# EPC_FRONTAL.net
KiCad netlist of a schematic drawn in EAGLE
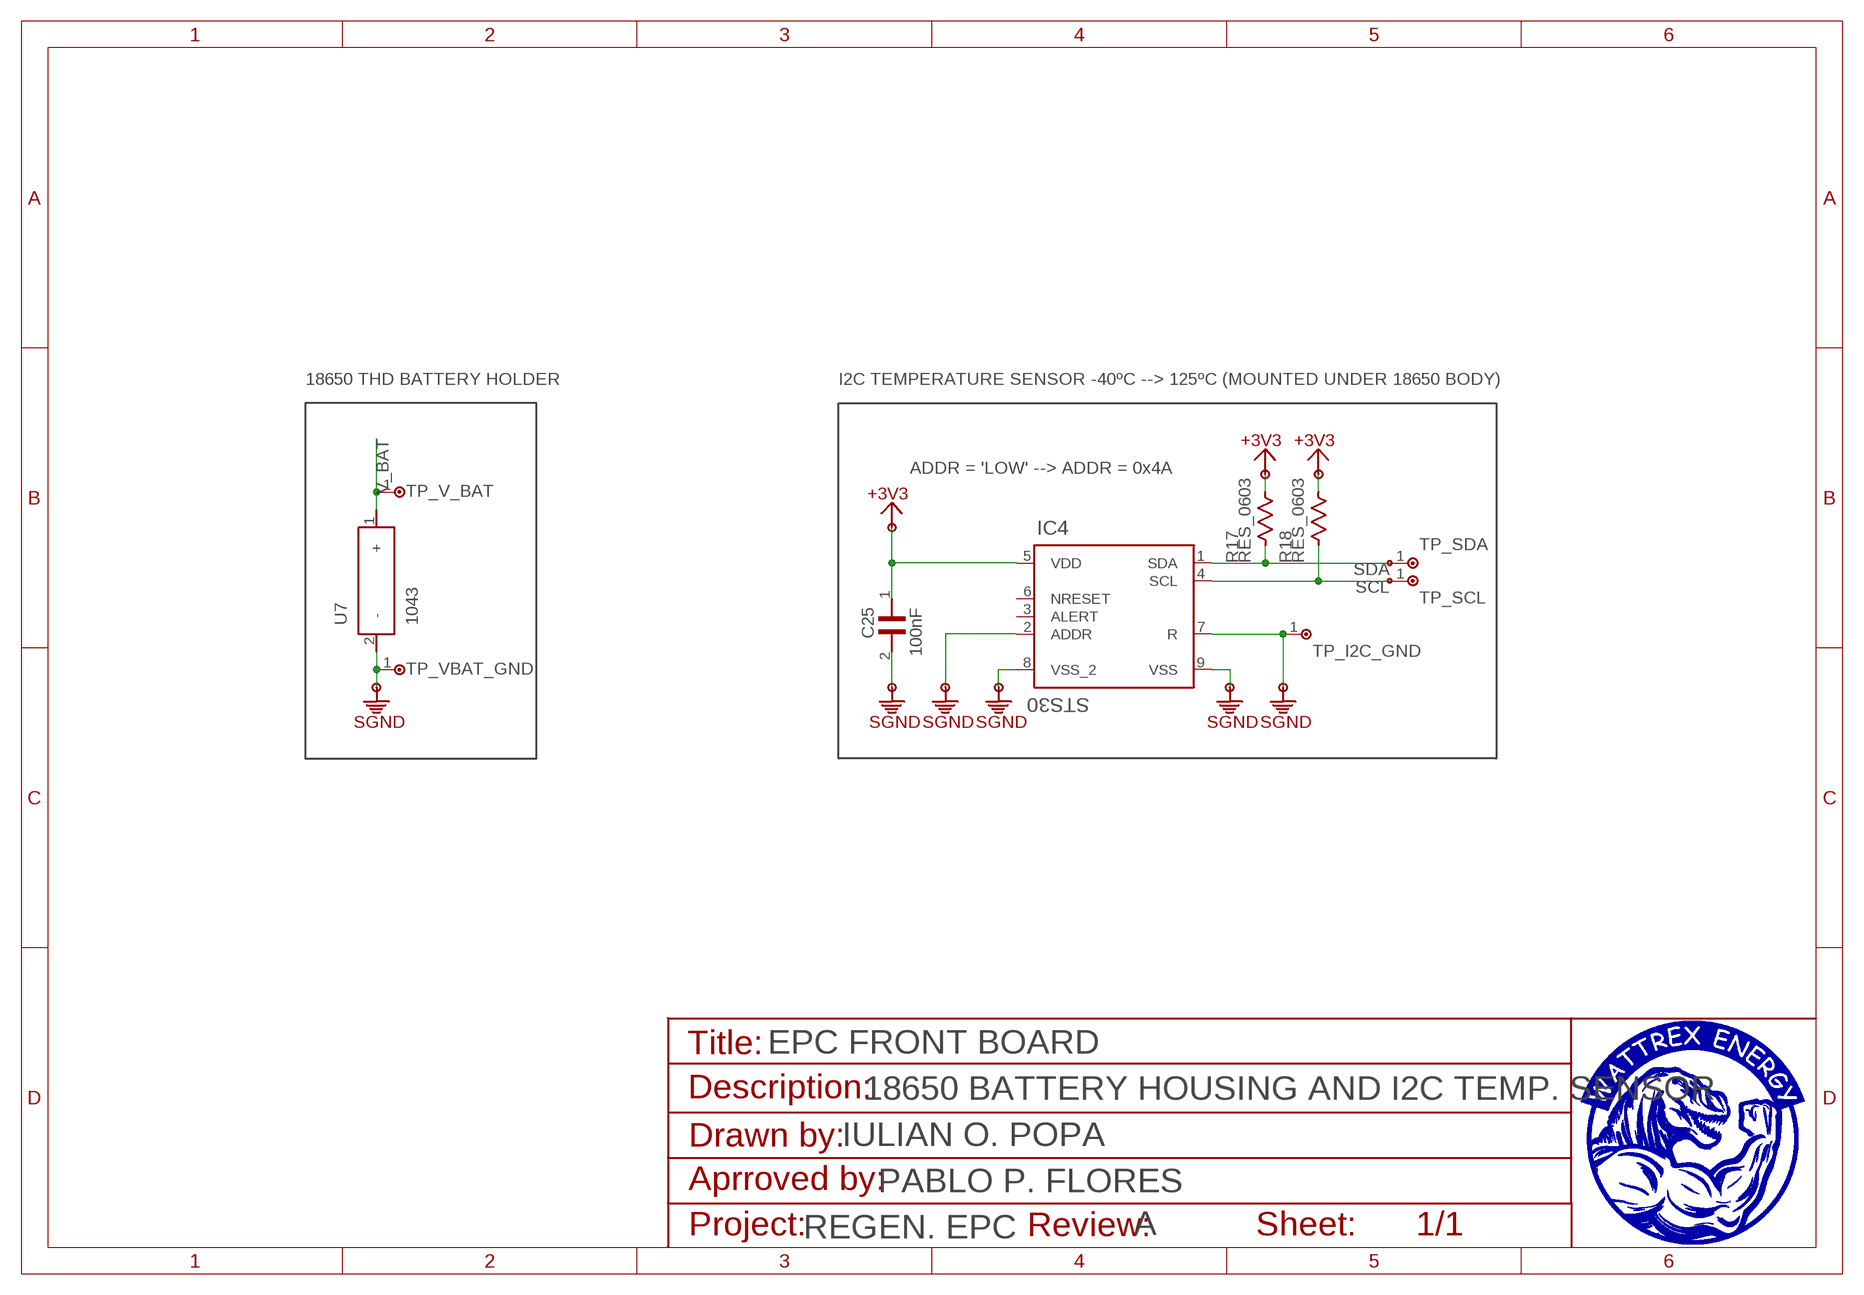
[diagram p0: schematic, sheet 1]

(export (version "E")
  (design (tool "Eeschema 10.0.6"))
  (components
    (comp (ref "C25")
      (value "100nF")
      (footprint "eagle-import:CAP_0603")
      (libsource (lib "eagle-import") (part "CAP_0603"))
    )
    (comp (ref "IC4")
      (value "STS30")
      (footprint "eagle-import:DFN")
      (fields
        (field (name "MANUFACTURER_PART_NUMBER") "STS30-DIS")
        (field (name "COPYRIGHT") "Copyright (C) 2022 Ultra Librarian. All rights reserved.")
      )
      (libsource (lib "eagle-import") (part "STS30-DISSTS3X-DIS_SEN-L"))
    )
    (comp (ref "R17")
      (value "RES_0603")
      (footprint "eagle-import:RES_0603")
      (libsource (lib "eagle-import") (part "RES_0603"))
    )
    (comp (ref "R18")
      (value "RES_0603")
      (footprint "eagle-import:RES_0603")
      (libsource (lib "eagle-import") (part "RES_0603"))
    )
    (comp (ref "TP_I2C_GND")
      (value "TP_S2751-46R")
      (footprint "eagle-import:TP_S2751-46R")
      (fields (field (name "MF") "Harwin Inc.") (field (name "MP") "S2751-46R"))
      (libsource (lib "eagle-import") (part "TP_S2751-46R"))
    )
    (comp (ref "TP_SCL")
      (value "TP_S2751-46R")
      (footprint "eagle-import:TP_S2751-46R")
      (fields (field (name "MF") "Harwin Inc.") (field (name "MP") "S2751-46R"))
      (libsource (lib "eagle-import") (part "TP_S2751-46R"))
    )
    (comp (ref "TP_SDA")
      (value "TP_S2751-46R")
      (footprint "eagle-import:TP_S2751-46R")
      (fields (field (name "MF") "Harwin Inc.") (field (name "MP") "S2751-46R"))
      (libsource (lib "eagle-import") (part "TP_S2751-46R"))
    )
    (comp (ref "TP_VBAT_GND")
      (value "TP_S2751-46R")
      (footprint "eagle-import:TP_S2751-46R")
      (fields (field (name "MF") "Harwin Inc.") (field (name "MP") "S2751-46R"))
      (libsource (lib "eagle-import") (part "TP_S2751-46R"))
    )
    (comp (ref "TP_V_BAT")
      (value "TP_S2751-46R")
      (footprint "eagle-import:TP_S2751-46R")
      (fields (field (name "MF") "Harwin Inc.") (field (name "MP") "S2751-46R"))
      (libsource (lib "eagle-import") (part "TP_S2751-46R"))
    )
    (comp (ref "U7")
      (value "1043")
      (footprint "eagle-import:1043")
      (fields (field (name "MOUSER_PART_NUMBER") "534-1043"))
      (libsource (lib "eagle-import") (part "1043"))
    )
  )
  (nets
    (net (code "1") (name "+3V3") (class "Default")
      (node (ref "C25") (pin "1") (pinfunction "1_1") (pintype "passive"))
      (node (ref "IC4") (pin "5") (pinfunction "VDD_5") (pintype "power_in"))
      (node (ref "R17") (pin "2") (pinfunction "P$2_2") (pintype "bidirectional"))
      (node (ref "R18") (pin "2") (pinfunction "P$2_2") (pintype "bidirectional"))
    )
    (net (code "2") (name "/SCL") (class "Default")
      (node (ref "IC4") (pin "4") (pinfunction "SCL_4") (pintype "bidirectional"))
      (node (ref "R18") (pin "1") (pinfunction "P$1_1") (pintype "bidirectional"))
      (node (ref "TP_SCL") (pin "1") (pinfunction "TP_1") (pintype "passive"))
    )
    (net (code "3") (name "/SDA") (class "Default")
      (node (ref "IC4") (pin "1") (pinfunction "SDA_1") (pintype "bidirectional"))
      (node (ref "R17") (pin "1") (pinfunction "P$1_1") (pintype "bidirectional"))
      (node (ref "TP_SDA") (pin "1") (pinfunction "TP_1") (pintype "passive"))
    )
    (net (code "4") (name "/V_BAT") (class "Default")
      (node (ref "TP_V_BAT") (pin "1") (pinfunction "TP_1") (pintype "passive"))
      (node (ref "U7") (pin "1") (pinfunction "+_1") (pintype "bidirectional"))
    )
    (net (code "5") (name "S_GND") (class "Default")
      (node (ref "C25") (pin "2") (pinfunction "2_2") (pintype "passive"))
      (node (ref "IC4") (pin "2") (pinfunction "ADDR_2") (pintype "input"))
      (node (ref "IC4") (pin "7") (pinfunction "R_7") (pintype "passive"))
      (node (ref "IC4") (pin "8") (pinfunction "VSS_2_8") (pintype "passive"))
      (node (ref "IC4") (pin "9") (pinfunction "VSS_9") (pintype "passive"))
      (node (ref "TP_I2C_GND") (pin "1") (pinfunction "TP_1") (pintype "passive"))
      (node (ref "TP_VBAT_GND") (pin "1") (pinfunction "TP_1") (pintype "passive"))
      (node (ref "U7") (pin "2") (pinfunction "-_2") (pintype "bidirectional"))
    )
    (net (code "6") (name "unconnected-(IC4-ALERT-Pad3)") (class "Default")
      (node (ref "IC4") (pin "3") (pinfunction "ALERT_3") (pintype "output"))
    )
    (net (code "7") (name "unconnected-(IC4-NRESET-Pad6)") (class "Default")
      (node (ref "IC4") (pin "6") (pinfunction "NRESET_6") (pintype "input"))
    )
  )
)
